# Aux_Inputs.net
KiCad netlist of a schematic drawn in Altium Designer
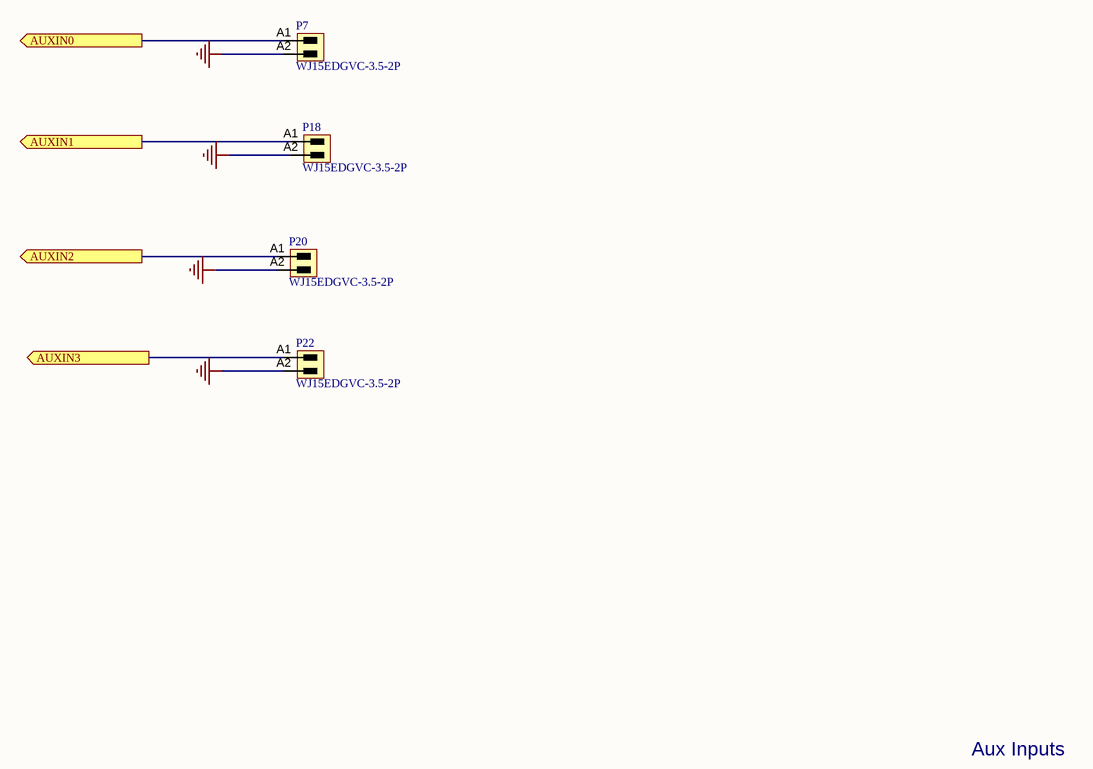
[diagram p0: Aux_Inputs.SchDoc]

(export (version "E")
  (design (tool "Eeschema 10.0.6"))
  (components
    (comp (ref "P7")
      (value "WJ15EDGVC-3.5-2P")
      (footprint "691321100002")
      (fields (field (name "MANUFACTURER") "Weidmueller"))
      (libsource (lib "Universal_CNC_Breakout") (part "3.5mm Terminal Header 2p"))
    )
    (comp (ref "P18")
      (value "WJ15EDGVC-3.5-2P")
      (footprint "691321100002")
      (fields (field (name "MANUFACTURER") "Weidmueller"))
      (libsource (lib "Universal_CNC_Breakout") (part "3.5mm Terminal Header 2p"))
    )
    (comp (ref "P20")
      (value "WJ15EDGVC-3.5-2P")
      (footprint "691321100002")
      (fields (field (name "MANUFACTURER") "Weidmueller"))
      (libsource (lib "Universal_CNC_Breakout") (part "3.5mm Terminal Header 2p"))
    )
    (comp (ref "P22")
      (value "WJ15EDGVC-3.5-2P")
      (footprint "691321100002")
      (fields (field (name "MANUFACTURER") "Weidmueller"))
      (libsource (lib "Universal_CNC_Breakout") (part "3.5mm Terminal Header 2p"))
    )
  )
  (nets
    (net (code "1") (name "/AUXIN0") (class "Default")
      (node (ref "P7") (pin "A1") (pinfunction "A1_A1") (pintype "passive"))
    )
    (net (code "2") (name "/AUXIN1") (class "Default")
      (node (ref "P18") (pin "A1") (pinfunction "A1_A1") (pintype "passive"))
    )
    (net (code "3") (name "/AUXIN2") (class "Default")
      (node (ref "P20") (pin "A1") (pinfunction "A1_A1") (pintype "passive"))
    )
    (net (code "4") (name "/AUXIN3") (class "Default")
      (node (ref "P22") (pin "A1") (pinfunction "A1_A1") (pintype "passive"))
    )
    (net (code "5") (name "GND") (class "Default")
      (node (ref "P18") (pin "A2") (pinfunction "A2_A2") (pintype "passive"))
      (node (ref "P20") (pin "A2") (pinfunction "A2_A2") (pintype "passive"))
      (node (ref "P22") (pin "A2") (pinfunction "A2_A2") (pintype "passive"))
      (node (ref "P7") (pin "A2") (pinfunction "A2_A2") (pintype "passive"))
    )
  )
)
